# USB.net
KiCad netlist of a schematic drawn in Altium Designer
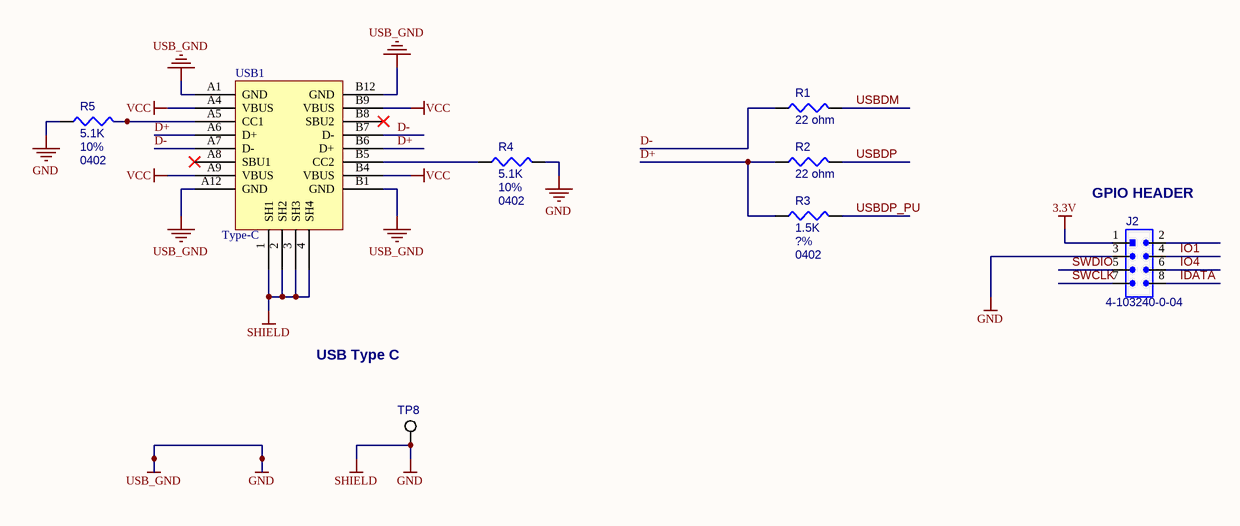
[diagram p0: USB.SchDoc]

(export (version "E")
  (design (tool "Eeschema 10.0.6"))
  (components
    (comp (ref "J2")
      (value "4-103240-0-04")
      (footprint "TRACKER:4-103240-0-04")
      (description "CONNECTOR, HEADER, 2X4, 0.1\" PITCH")
      (fields (field (name "MANUFACTURER") "TE CONNECTIVITY"))
      (libsource (lib "TRACKER") (part "4-103240-0-04"))
    )
    (comp (ref "R1")
      (value "22 ohm")
      (footprint "RESISTOR_0402")
      (description "RES, 22 OHM, 1/10W, ?%, 0402")
      (fields (field (name "MANUFACTURER") "PANASONIC") (field (name "PART NUMBER") "ERJ-2RKF22R0X"))
      (libsource (lib "TRACKER") (part "RESISTOR"))
    )
    (comp (ref "R2")
      (value "22 ohm")
      (footprint "RESISTOR_0402")
      (description "RES, 22 OHM, 1/10W, ?%, 0402")
      (fields (field (name "MANUFACTURER") "PANASONIC") (field (name "PART NUMBER") "ERJ-2RKF22R0X"))
      (libsource (lib "TRACKER") (part "RESISTOR"))
    )
    (comp (ref "R3")
      (value "1.5K")
      (footprint "RESISTOR_0402")
      (description "RES, 1.5K OHM, 1/10W, ?%, 0402")
      (fields
        (field (name "MANUFACTURER") "PANASONIC")
        (field (name "PART NUMBER") "ERJ-2RKF1501X")
        (field (name "PACKAGE") "0402")
        (field (name "TOLERANCE") "?%")
      )
      (libsource (lib "TRACKER") (part "RESISTOR"))
    )
    (comp (ref "R4")
      (value "5.1K")
      (footprint "RES_0402")
      (description "RES, 1.5K OHM, 1/10W, ?%, 0402")
      (fields
        (field (name "MANUFACTURER") "PANASONIC")
        (field (name "PART NUMBER") "ERJ-2RKF1501X")
        (field (name "PACKAGE") "0402")
        (field (name "TOLERANCE") "10%")
      )
      (libsource (lib "TRACKER") (part "RESISTOR"))
    )
    (comp (ref "R5")
      (value "5.1K")
      (footprint "RES_0402")
      (description "RES, 1.5K OHM, 1/10W, ?%, 0402")
      (fields
        (field (name "MANUFACTURER") "PANASONIC")
        (field (name "PART NUMBER") "ERJ-2RKF1501X")
        (field (name "PACKAGE") "0402")
        (field (name "误差") "10%")
      )
      (libsource (lib "TRACKER") (part "RESISTOR"))
    )
    (comp (ref "TP8")
      (value "TEST POINT")
      (footprint "TEST_POINT_PAD")
      (libsource (lib "TRACKER") (part "TEST_POINT"))
    )
    (comp (ref "USB1")
      (value "Type-C")
      (footprint "Type-C-TOP")
      (description "16脚USB TypeC")
      (libsource (lib "GeekTechLib") (part "USB-Type-C-TOP-16P"))
    )
  )
  (nets
    (net (code "1") (name "/D+") (class "Default")
      (node (ref "R2") (pin "1") (pinfunction "1_1") (pintype "passive"))
      (node (ref "R3") (pin "1") (pinfunction "1_1") (pintype "passive"))
      (node (ref "USB1") (pin "A6") (pinfunction "D+_A6") (pintype "passive"))
      (node (ref "USB1") (pin "B6") (pinfunction "D+_B6") (pintype "passive"))
    )
    (net (code "2") (name "/D-") (class "Default")
      (node (ref "R1") (pin "1") (pinfunction "1_1") (pintype "passive"))
      (node (ref "USB1") (pin "A7") (pinfunction "D-_A7") (pintype "passive"))
      (node (ref "USB1") (pin "B7") (pinfunction "D-_B7") (pintype "passive"))
    )
    (net (code "3") (name "/IDATA") (class "Default") (node (ref "J2") (pin "8") (pintype "passive")))
    (net (code "4") (name "/IO1") (class "Default") (node (ref "J2") (pin "4") (pintype "passive")))
    (net (code "5") (name "/IO4") (class "Default") (node (ref "J2") (pin "6") (pintype "passive")))
    (net (code "6") (name "/SWCLK") (class "Default") (node (ref "J2") (pin "7") (pintype "passive")))
    (net (code "7") (name "/SWDIO") (class "Default") (node (ref "J2") (pin "5") (pintype "passive")))
    (net (code "8") (name "/USBDM") (class "Default")
      (node (ref "R1") (pin "2") (pinfunction "2_2") (pintype "passive"))
    )
    (net (code "9") (name "/USBDP") (class "Default")
      (node (ref "R2") (pin "2") (pinfunction "2_2") (pintype "passive"))
    )
    (net (code "10") (name "/USBDP_PU") (class "Default")
      (node (ref "R3") (pin "2") (pinfunction "2_2") (pintype "passive"))
    )
    (net (code "11") (name "3.3V") (class "Default") (node (ref "J2") (pin "1") (pintype "passive")))
    (net (code "12") (name "GND") (class "Default")
      (node (ref "J2") (pin "3") (pintype "passive"))
      (node (ref "R4") (pin "2") (pinfunction "2_2") (pintype "passive"))
      (node (ref "R5") (pin "1") (pinfunction "1_1") (pintype "passive"))
      (node (ref "TP8") (pin "1") (pinfunction "1_1") (pintype "passive"))
      (node (ref "USB1") (pin "1") (pinfunction "SH1_1") (pintype "passive"))
      (node (ref "USB1") (pin "2") (pinfunction "SH2_2") (pintype "passive"))
      (node (ref "USB1") (pin "3") (pinfunction "SH3_3") (pintype "passive"))
      (node (ref "USB1") (pin "4") (pinfunction "SH4_4") (pintype "passive"))
      (node (ref "USB1") (pin "A1") (pinfunction "GND_A1") (pintype "passive"))
      (node (ref "USB1") (pin "A12") (pinfunction "GND_A12") (pintype "passive"))
      (node (ref "USB1") (pin "B1") (pinfunction "GND_B1") (pintype "passive"))
      (node (ref "USB1") (pin "B12") (pinfunction "GND_B12") (pintype "passive"))
    )
    (net (code "13") (name "Net-(USB1-CC1)") (class "Default")
      (node (ref "R5") (pin "2") (pinfunction "2_2") (pintype "passive"))
      (node (ref "USB1") (pin "A5") (pinfunction "CC1_A5") (pintype "passive"))
    )
    (net (code "14") (name "Net-(USB1-CC2)") (class "Default")
      (node (ref "R4") (pin "1") (pinfunction "1_1") (pintype "passive"))
      (node (ref "USB1") (pin "B5") (pinfunction "CC2_B5") (pintype "passive"))
    )
    (net (code "15") (name "VCC") (class "Default")
      (node (ref "USB1") (pin "A4") (pinfunction "VBUS_A4") (pintype "passive"))
      (node (ref "USB1") (pin "A9") (pinfunction "VBUS_A9") (pintype "passive"))
      (node (ref "USB1") (pin "B4") (pinfunction "VBUS_B4") (pintype "passive"))
      (node (ref "USB1") (pin "B9") (pinfunction "VBUS_B9") (pintype "passive"))
    )
    (net (code "16") (name "unconnected-(J2-Pad2)") (class "Default")
      (node (ref "J2") (pin "2") (pintype "passive"))
    )
    (net (code "17") (name "unconnected-(USB1-SBU1-PadA8)") (class "Default")
      (node (ref "USB1") (pin "A8") (pinfunction "SBU1_A8") (pintype "passive+no_connect"))
    )
    (net (code "18") (name "unconnected-(USB1-SBU2-PadB8)") (class "Default")
      (node (ref "USB1") (pin "B8") (pinfunction "SBU2_B8") (pintype "passive+no_connect"))
    )
  )
)
